# reflip_1_3.net
KiCad netlist of a schematic drawn in EAGLE
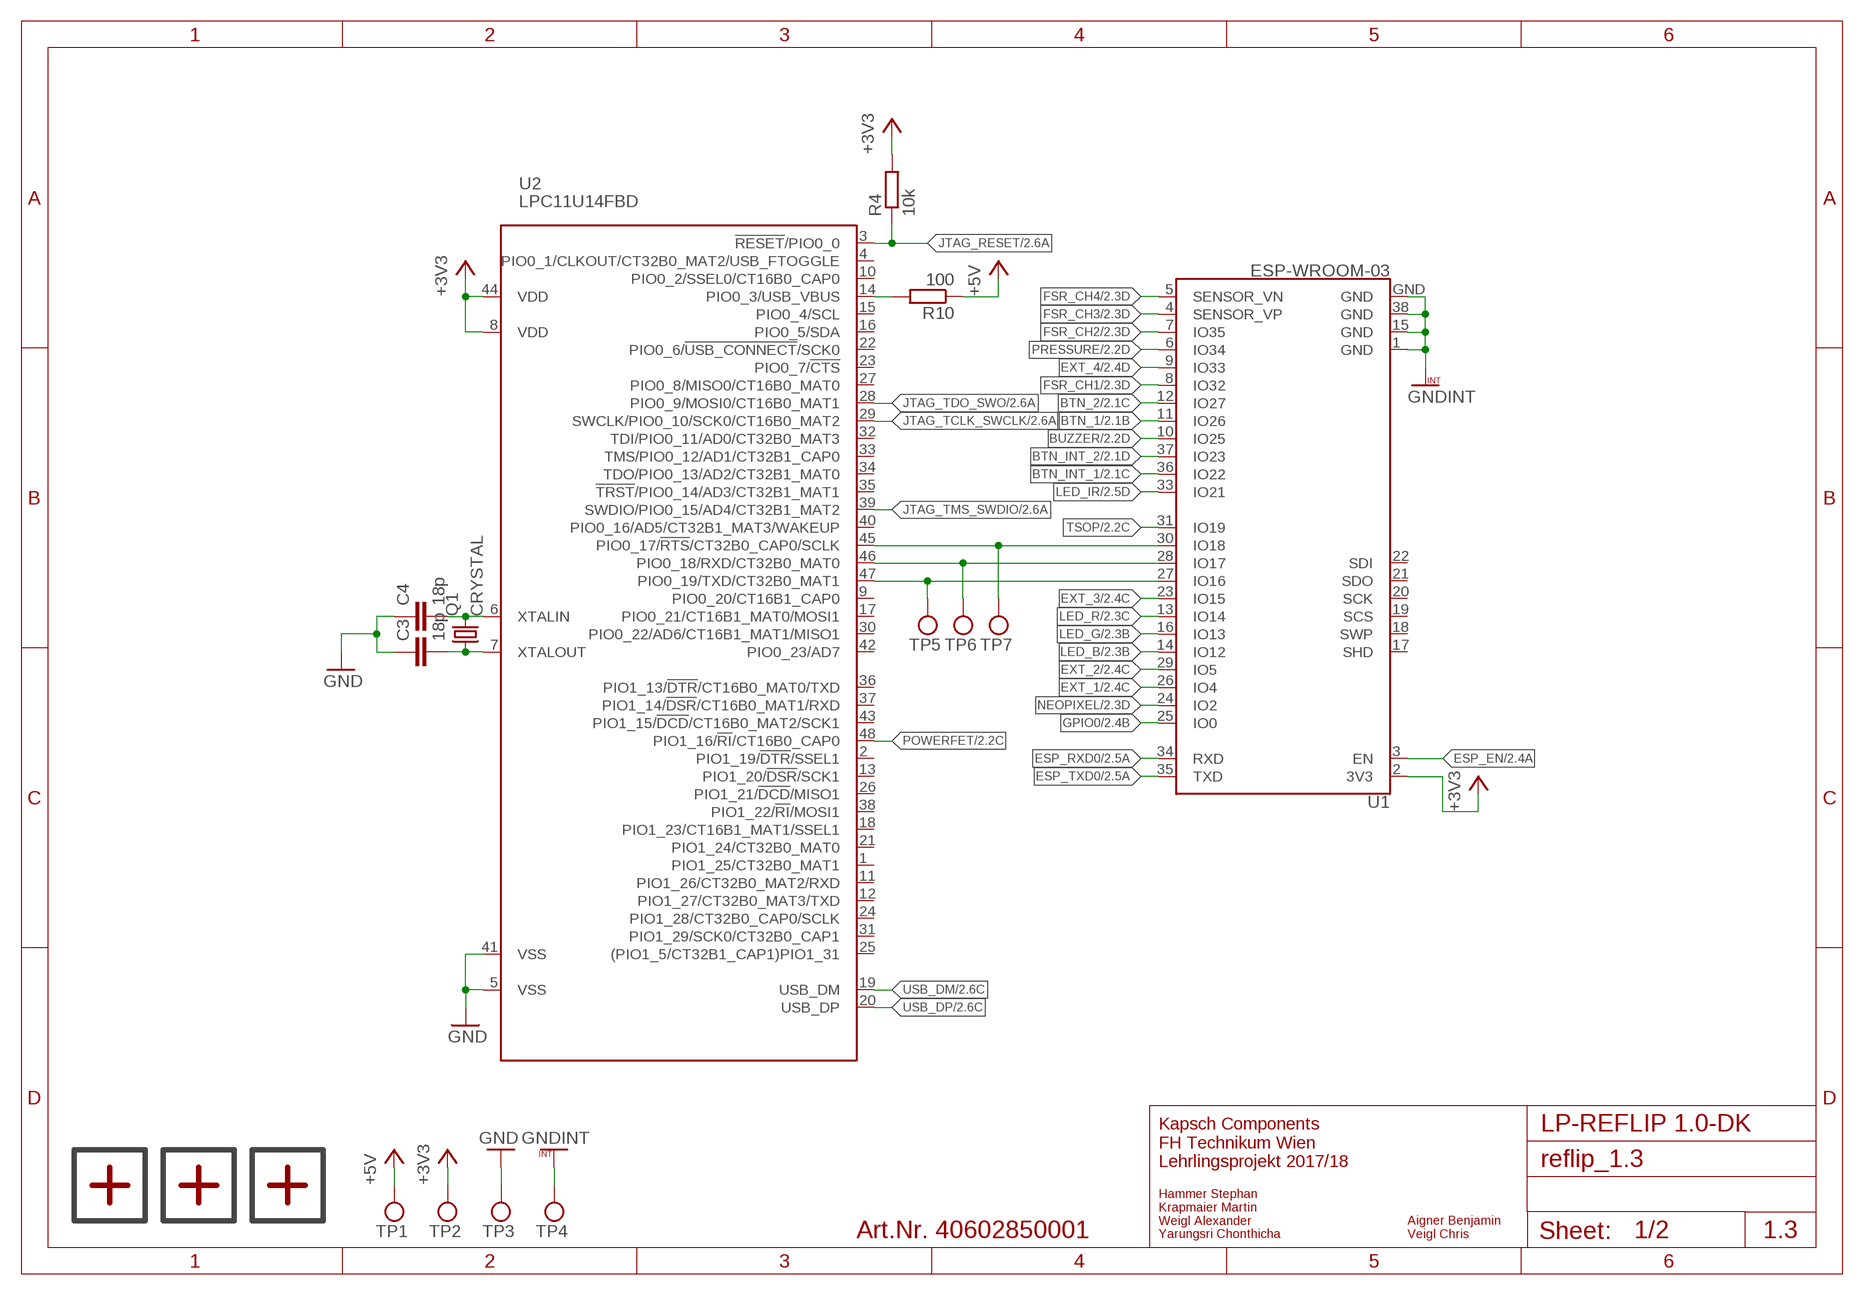
[diagram p0: schematic, sheet 1]
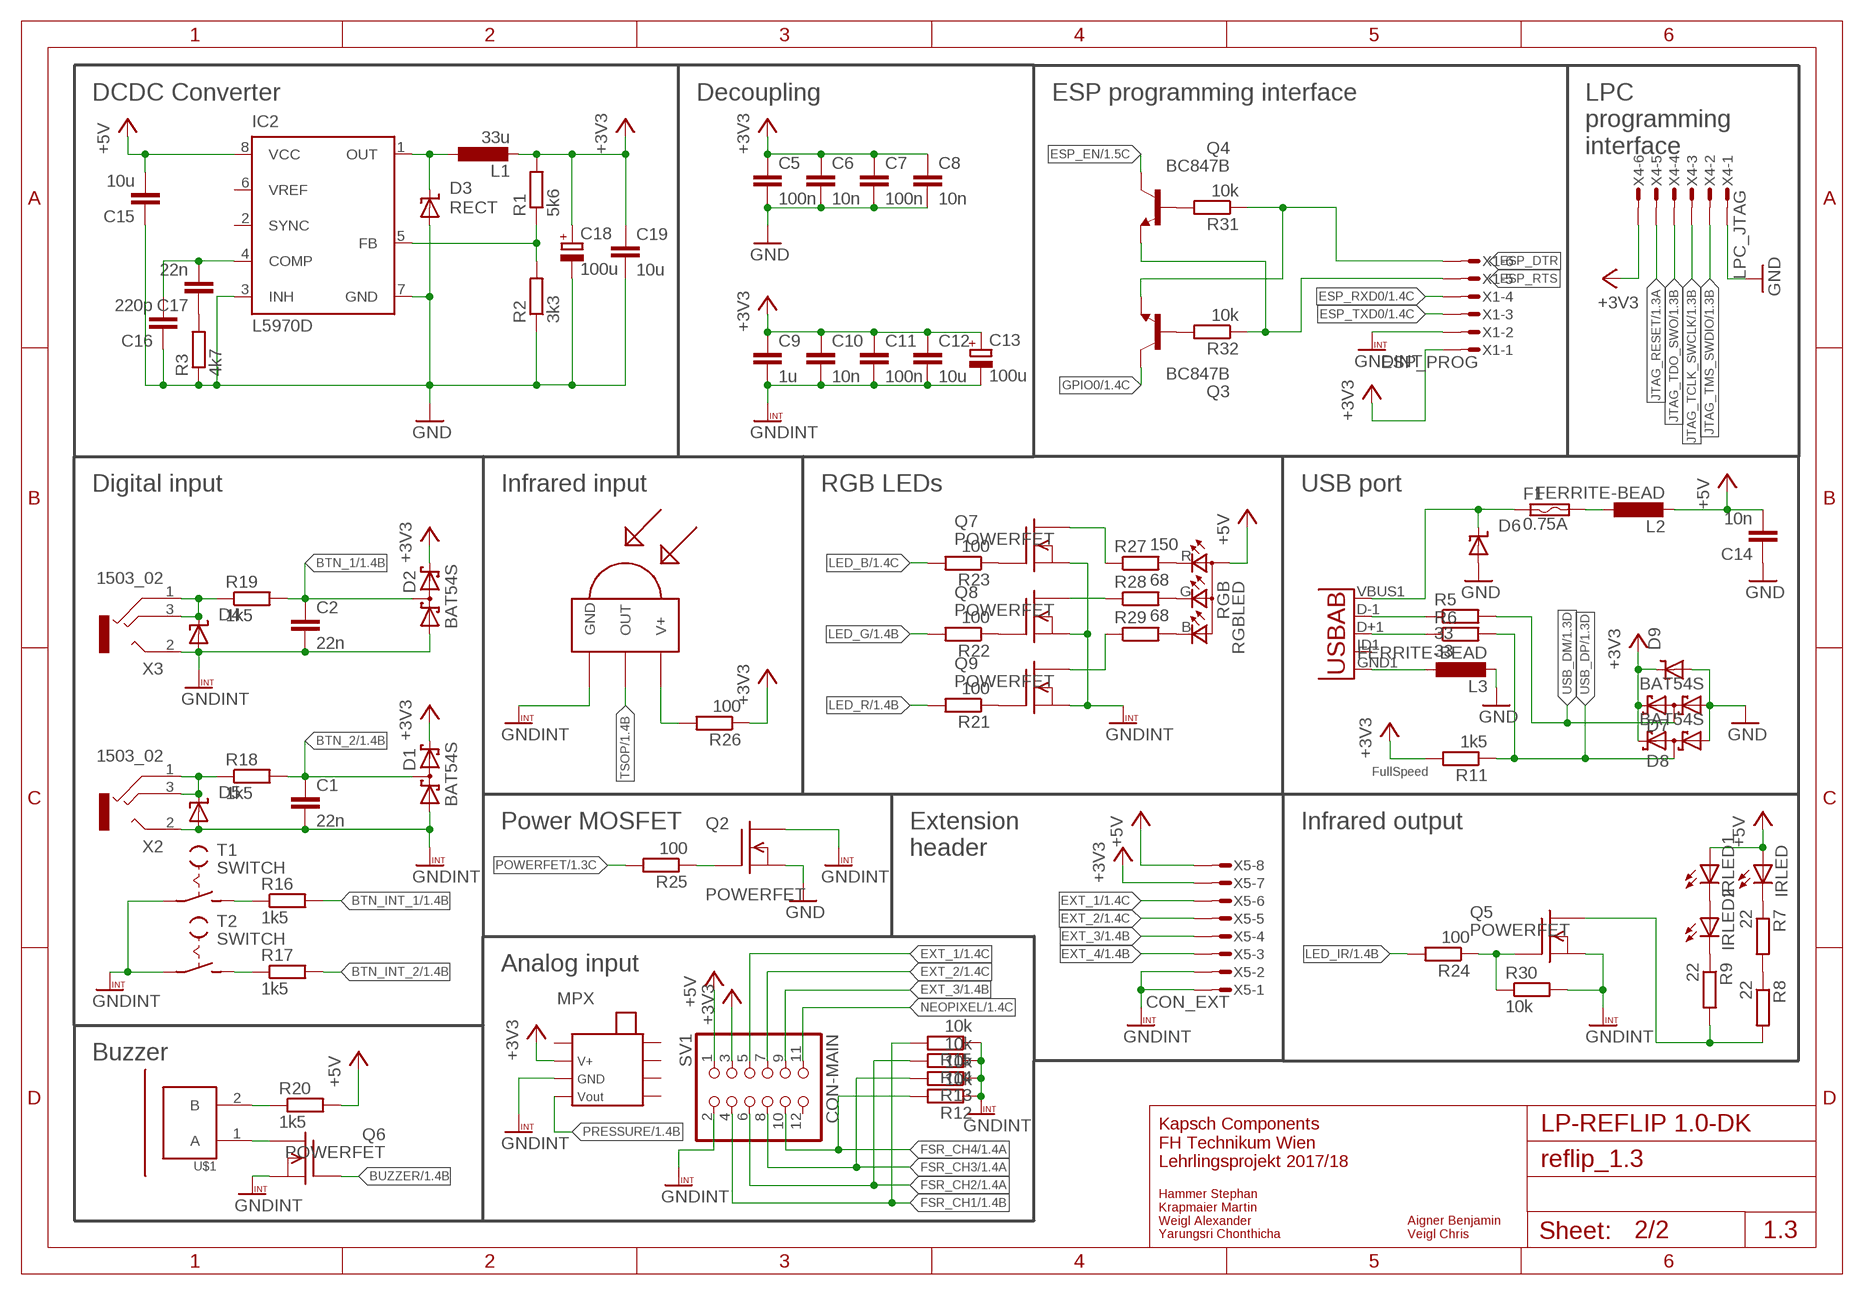
[diagram p1: schematic, sheet 2]

(export (version "E")
  (design (tool "Eeschema 10.0.6"))
  (components
    (comp (ref "C1")
      (value "22n")
      (footprint "eagle-import:C0603")
      (libsource (lib "eagle-import") (part "C-EUC0603"))
    )
    (comp (ref "C2")
      (value "22n")
      (footprint "eagle-import:C0603")
      (libsource (lib "eagle-import") (part "C-EUC0603"))
    )
    (comp (ref "C5")
      (value "100n")
      (footprint "eagle-import:C0603")
      (libsource (lib "eagle-import") (part "C-EUC0603"))
    )
    (comp (ref "C6")
      (value "10n")
      (footprint "eagle-import:C0603")
      (libsource (lib "eagle-import") (part "C-EUC0603"))
    )
    (comp (ref "C7")
      (value "100n")
      (footprint "eagle-import:C0603")
      (libsource (lib "eagle-import") (part "C-EUC0603"))
    )
    (comp (ref "C8")
      (value "10n")
      (footprint "eagle-import:C0603")
      (libsource (lib "eagle-import") (part "C-EUC0603"))
    )
    (comp (ref "C9")
      (value "1u")
      (footprint "eagle-import:C0603")
      (libsource (lib "eagle-import") (part "C-EUC0603"))
    )
    (comp (ref "C10")
      (value "10n")
      (footprint "eagle-import:C0603")
      (libsource (lib "eagle-import") (part "C-EUC0603"))
    )
    (comp (ref "C11")
      (value "100n")
      (footprint "eagle-import:C0603")
      (libsource (lib "eagle-import") (part "C-EUC0603"))
    )
    (comp (ref "C12")
      (value "10u")
      (footprint "eagle-import:C0603")
      (libsource (lib "eagle-import") (part "C-EUC0603"))
    )
    (comp (ref "C13")
      (value "100u")
      (footprint "eagle-import:PANASONIC_D")
      (libsource (lib "eagle-import") (part "CPOL-EUD"))
    )
    (comp (ref "C14")
      (value "10n")
      (footprint "eagle-import:C0603")
      (libsource (lib "eagle-import") (part "C-EUC0603"))
    )
    (comp (ref "C15")
      (value "10u")
      (footprint "eagle-import:C0603")
      (libsource (lib "eagle-import") (part "C-EUC0603"))
    )
    (comp (ref "C16")
      (value "220p")
      (footprint "eagle-import:C0603")
      (libsource (lib "eagle-import") (part "C-EUC0603"))
    )
    (comp (ref "C17")
      (value "22n")
      (footprint "eagle-import:C0603")
      (libsource (lib "eagle-import") (part "C-EUC0603"))
    )
    (comp (ref "C18")
      (value "100u")
      (footprint "eagle-import:PANASONIC_D")
      (libsource (lib "eagle-import") (part "CPOL-EUD"))
    )
    (comp (ref "C19")
      (value "10u")
      (footprint "eagle-import:C0603")
      (libsource (lib "eagle-import") (part "C-EUC0603"))
    )
    (comp (ref "D1")
      (value "BAT54S")
      (footprint "eagle-import:SOT23")
      (libsource (lib "eagle-import") (part "BAT54S"))
    )
    (comp (ref "D2")
      (value "BAT54S")
      (footprint "eagle-import:SOT23")
      (libsource (lib "eagle-import") (part "BAT54S"))
    )
    (comp (ref "D3")
      (value "RECT")
      (footprint "eagle-import:SMBJ")
      (libsource (lib "eagle-import") (part "RECT"))
    )
    (comp (ref "D4")
      (value "TVS-DIODE")
      (footprint "eagle-import:SMBJ")
      (libsource (lib "eagle-import") (part "TVS-DIODE"))
    )
    (comp (ref "D5")
      (value "TVS-DIODE")
      (footprint "eagle-import:SMBJ")
      (libsource (lib "eagle-import") (part "TVS-DIODE"))
    )
    (comp (ref "D6")
      (value "TVS-DIODE")
      (footprint "eagle-import:SMBJ")
      (libsource (lib "eagle-import") (part "TVS-DIODE"))
    )
    (comp (ref "D7")
      (value "BAT54S")
      (footprint "eagle-import:SOT23")
      (libsource (lib "eagle-import") (part "BAT54S"))
    )
    (comp (ref "D8")
      (value "BAT54S")
      (footprint "eagle-import:SOT23")
      (libsource (lib "eagle-import") (part "BAT54S"))
    )
    (comp (ref "D9")
      (value "TVS-DIODE")
      (footprint "eagle-import:SMBJ")
      (libsource (lib "eagle-import") (part "TVS-DIODE"))
    )
    (comp (ref "F1")
      (value "0.75A")
      (footprint "eagle-import:FUSE")
      (libsource (lib "eagle-import") (part "FUSE"))
    )
    (comp (ref "IC2")
      (value "L5970D")
      (footprint "eagle-import:HSOP8")
      (fields (field (name "MF") "STMICROELECTRONICS") (field (name "MPN") "L5973D"))
      (libsource (lib "eagle-import") (part "L5973D"))
    )
    (comp (ref "IRLED")
      (value "IRLED")
      (footprint "eagle-import:IRLED")
      (libsource (lib "eagle-import") (part "IRLED"))
    )
    (comp (ref "IRLED1")
      (value "IRLED")
      (footprint "eagle-import:IRLED")
      (libsource (lib "eagle-import") (part "IRLED"))
    )
    (comp (ref "IRLED2")
      (value "IRLED")
      (footprint "eagle-import:IRLED")
      (libsource (lib "eagle-import") (part "IRLED"))
    )
    (comp (ref "L1")
      (value "33u")
      (footprint "eagle-import:SPULE")
      (libsource (lib "eagle-import") (part "SPULE"))
    )
    (comp (ref "L2")
      (value "FERRITE-BEAD")
      (footprint "eagle-import:FERRITEBEAD")
      (libsource (lib "eagle-import") (part "FERRITE-BEAD"))
    )
    (comp (ref "L3")
      (value "FERRITE-BEAD")
      (footprint "eagle-import:FERRITEBEAD")
      (libsource (lib "eagle-import") (part "FERRITE-BEAD"))
    )
    (comp (ref "MPX")
      (value "MPX_PRESSURE_SENSOR")
      (footprint "eagle-import:MPX_PRESSURE_SENSOR")
      (libsource (lib "eagle-import") (part "MPX_PRESSURE_SENSOR"))
    )
    (comp (ref "Q2")
      (value "POWERFET")
      (footprint "eagle-import:SOT-23")
      (libsource (lib "eagle-import") (part "POWERFET"))
    )
    (comp (ref "Q3")
      (value "BC847B")
      (footprint "eagle-import:SOT23")
      (libsource (lib "eagle-import") (part "BC847B"))
    )
    (comp (ref "Q4")
      (value "BC847B")
      (footprint "eagle-import:SOT23")
      (libsource (lib "eagle-import") (part "BC847B"))
    )
    (comp (ref "Q5")
      (value "POWERFET")
      (footprint "eagle-import:SOT-23")
      (libsource (lib "eagle-import") (part "POWERFET"))
    )
    (comp (ref "Q6")
      (value "POWERFET")
      (footprint "eagle-import:SOT-23")
      (libsource (lib "eagle-import") (part "POWERFET"))
    )
    (comp (ref "Q7")
      (value "POWERFET")
      (footprint "eagle-import:SOT-23")
      (libsource (lib "eagle-import") (part "POWERFET"))
    )
    (comp (ref "Q8")
      (value "POWERFET")
      (footprint "eagle-import:SOT-23")
      (libsource (lib "eagle-import") (part "POWERFET"))
    )
    (comp (ref "Q9")
      (value "POWERFET")
      (footprint "eagle-import:SOT-23")
      (libsource (lib "eagle-import") (part "POWERFET"))
    )
    (comp (ref "R1")
      (value "5k6")
      (footprint "eagle-import:R0603")
      (libsource (lib "eagle-import") (part "R-EU_R0603"))
    )
    (comp (ref "R2")
      (value "3k3")
      (footprint "eagle-import:R0603")
      (libsource (lib "eagle-import") (part "R-EU_R0603"))
    )
    (comp (ref "R3")
      (value "4k7")
      (footprint "eagle-import:R0603")
      (libsource (lib "eagle-import") (part "R-EU_R0603"))
    )
    (comp (ref "R5")
      (value "33")
      (footprint "eagle-import:R0603")
      (libsource (lib "eagle-import") (part "R-EU_R0603"))
    )
    (comp (ref "R6")
      (value "33")
      (footprint "eagle-import:R0603")
      (libsource (lib "eagle-import") (part "R-EU_R0603"))
    )
    (comp (ref "R7")
      (value "22")
      (footprint "eagle-import:R1206")
      (libsource (lib "eagle-import") (part "R-EU_R1206"))
    )
    (comp (ref "R8")
      (value "22")
      (footprint "eagle-import:R1206")
      (libsource (lib "eagle-import") (part "R-EU_R1206"))
    )
    (comp (ref "R9")
      (value "22")
      (footprint "eagle-import:R1206")
      (libsource (lib "eagle-import") (part "R-EU_R1206"))
    )
    (comp (ref "R11")
      (value "1k5")
      (footprint "eagle-import:R0603")
      (libsource (lib "eagle-import") (part "R-EU_R0603"))
    )
    (comp (ref "R12")
      (value "10k")
      (footprint "eagle-import:R0603")
      (libsource (lib "eagle-import") (part "R-EU_R0603"))
    )
    (comp (ref "R13")
      (value "10k")
      (footprint "eagle-import:R0603")
      (libsource (lib "eagle-import") (part "R-EU_R0603"))
    )
    (comp (ref "R14")
      (value "10k")
      (footprint "eagle-import:R0603")
      (libsource (lib "eagle-import") (part "R-EU_R0603"))
    )
    (comp (ref "R15")
      (value "10k")
      (footprint "eagle-import:R0603")
      (libsource (lib "eagle-import") (part "R-EU_R0603"))
    )
    (comp (ref "R16")
      (value "1k5")
      (footprint "eagle-import:R0603")
      (libsource (lib "eagle-import") (part "R-EU_R0603"))
    )
    (comp (ref "R17")
      (value "1k5")
      (footprint "eagle-import:R0603")
      (libsource (lib "eagle-import") (part "R-EU_R0603"))
    )
    (comp (ref "R18")
      (value "1k5")
      (footprint "eagle-import:R0603")
      (libsource (lib "eagle-import") (part "R-EU_R0603"))
    )
    (comp (ref "R19")
      (value "1k5")
      (footprint "eagle-import:R0603")
      (libsource (lib "eagle-import") (part "R-EU_R0603"))
    )
    (comp (ref "R20")
      (value "1k5")
      (footprint "eagle-import:R0603")
      (libsource (lib "eagle-import") (part "R-EU_R0603"))
    )
    (comp (ref "R21")
      (value "100")
      (footprint "eagle-import:R0603")
      (libsource (lib "eagle-import") (part "R-EU_R0603"))
    )
    (comp (ref "R22")
      (value "100")
      (footprint "eagle-import:R0603")
      (libsource (lib "eagle-import") (part "R-EU_R0603"))
    )
    (comp (ref "R23")
      (value "100")
      (footprint "eagle-import:R0603")
      (libsource (lib "eagle-import") (part "R-EU_R0603"))
    )
    (comp (ref "R24")
      (value "100")
      (footprint "eagle-import:R0603")
      (libsource (lib "eagle-import") (part "R-EU_R0603"))
    )
    (comp (ref "R25")
      (value "100")
      (footprint "eagle-import:R0603")
      (libsource (lib "eagle-import") (part "R-EU_R0603"))
    )
    (comp (ref "R26")
      (value "100")
      (footprint "eagle-import:R0603")
      (libsource (lib "eagle-import") (part "R-EU_R0603"))
    )
    (comp (ref "R27")
      (value "150")
      (footprint "eagle-import:R0603")
      (libsource (lib "eagle-import") (part "R-EU_R0603"))
    )
    (comp (ref "R28")
      (value "68")
      (footprint "eagle-import:R0603")
      (libsource (lib "eagle-import") (part "R-EU_R0603"))
    )
    (comp (ref "R29")
      (value "68")
      (footprint "eagle-import:R0603")
      (libsource (lib "eagle-import") (part "R-EU_R0603"))
    )
    (comp (ref "R30")
      (value "10k")
      (footprint "eagle-import:R0603")
      (libsource (lib "eagle-import") (part "R-EU_R0603"))
    )
    (comp (ref "R31")
      (value "10k")
      (footprint "eagle-import:R0603")
      (libsource (lib "eagle-import") (part "R-EU_R0603"))
    )
    (comp (ref "R32")
      (value "10k")
      (footprint "eagle-import:R0603")
      (libsource (lib "eagle-import") (part "R-EU_R0603"))
    )
    (comp (ref "RGB")
      (value "RGBLED")
      (footprint "eagle-import:RGBLED")
      (libsource (lib "eagle-import") (part "RGBLED"))
    )
    (comp (ref "SV1")
      (value "CON-MAIN")
      (footprint "eagle-import:FE06-2W")
      (libsource (lib "eagle-import") (part "CON-MAIN"))
    )
    (comp (ref "T1")
      (value "SWITCH")
      (footprint "eagle-import:SWITCHES")
      (libsource (lib "eagle-import") (part "SWITCH"))
    )
    (comp (ref "T2")
      (value "SWITCH")
      (footprint "eagle-import:SWITCHES")
      (libsource (lib "eagle-import") (part "SWITCH"))
    )
    (comp (ref "U$1")
      (value "PKLCS1212E2400-R1")
      (footprint "eagle-import:BUZZ_PIEZO_SMD")
      (libsource (lib "eagle-import") (part "PKLCS1212E2400-R1"))
    )
    (comp (ref "U$2")
      (value "TSOP4838")
      (footprint "eagle-import:TSOP18XX")
      (libsource (lib "eagle-import") (part "TSOP4838"))
    )
    (comp (ref "U3")
      (value "USB\"\"")
      (footprint "eagle-import:USB-MICRO-SMD")
      (libsource (lib "eagle-import") (part "USB{dblquote}{dblquote}"))
    )
    (comp (ref "X1")
      (value "ESP_PROG")
      (footprint "eagle-import:MICROMATCH-6SMD")
      (libsource (lib "eagle-import") (part "MICROMATCH-6SMD"))
    )
    (comp (ref "X2")
      (value "1503_02")
      (footprint "eagle-import:1503_02")
      (libsource (lib "eagle-import") (part "1503_02"))
    )
    (comp (ref "X3")
      (value "1503_02")
      (footprint "eagle-import:1503_02")
      (libsource (lib "eagle-import") (part "1503_02"))
    )
    (comp (ref "X4")
      (value "LPC_JTAG")
      (footprint "eagle-import:MICROMATCH-6SMD")
      (libsource (lib "eagle-import") (part "MICROMATCH-6SMD"))
    )
    (comp (ref "X5")
      (value "CON_EXT")
      (footprint "eagle-import:MICROMATCH-8-SMD")
      (libsource (lib "eagle-import") (part "MICROMATCH-8SMD"))
    )
    (comp (ref "C3")
      (value "18p")
      (footprint "eagle-import:C0603")
      (libsource (lib "eagle-import") (part "C-EUC0603"))
    )
    (comp (ref "C4")
      (value "18p")
      (footprint "eagle-import:C0603")
      (libsource (lib "eagle-import") (part "C-EUC0603"))
    )
    (comp (ref "Q1")
      (value "CRYSTAL")
      (footprint "eagle-import:CRYSTAL")
      (libsource (lib "eagle-import") (part "CRYSTAL"))
    )
    (comp (ref "R4")
      (value "10k")
      (footprint "eagle-import:R0603")
      (libsource (lib "eagle-import") (part "R-EU_R0603"))
    )
    (comp (ref "R10")
      (value "100")
      (footprint "eagle-import:R0603")
      (libsource (lib "eagle-import") (part "R-EU_R0603"))
    )
    (comp (ref "U$3")
      (value "PASSMARKE")
      (footprint "eagle-import:PASSMARKE")
      (libsource (lib "eagle-import") (part "PASSMARKE"))
    )
    (comp (ref "U$4")
      (value "PASSMARKE")
      (footprint "eagle-import:PASSMARKE")
      (libsource (lib "eagle-import") (part "PASSMARKE"))
    )
    (comp (ref "U$5")
      (value "PASSMARKE")
      (footprint "eagle-import:PASSMARKE")
      (libsource (lib "eagle-import") (part "PASSMARKE"))
    )
    (comp (ref "U$6")
      (value "TP1")
      (footprint "eagle-import:TESTPUNKT")
      (libsource (lib "eagle-import") (part "TESTPUNKT"))
    )
    (comp (ref "U$7")
      (value "TP2")
      (footprint "eagle-import:TESTPUNKT")
      (libsource (lib "eagle-import") (part "TESTPUNKT"))
    )
    (comp (ref "U$8")
      (value "TP3")
      (footprint "eagle-import:TESTPUNKT")
      (libsource (lib "eagle-import") (part "TESTPUNKT"))
    )
    (comp (ref "U$9")
      (value "TP4")
      (footprint "eagle-import:TESTPUNKT")
      (libsource (lib "eagle-import") (part "TESTPUNKT"))
    )
    (comp (ref "U$10")
      (value "TP7")
      (footprint "eagle-import:TESTPUNKT")
      (libsource (lib "eagle-import") (part "TESTPUNKT"))
    )
    (comp (ref "U$11")
      (value "TP6")
      (footprint "eagle-import:TESTPUNKT")
      (libsource (lib "eagle-import") (part "TESTPUNKT"))
    )
    (comp (ref "U$12")
      (value "TP5")
      (footprint "eagle-import:TESTPUNKT")
      (libsource (lib "eagle-import") (part "TESTPUNKT"))
    )
    (comp (ref "U1")
      (value "ESP-WROOM-03")
      (footprint "eagle-import:ESP-WROOM-03")
      (libsource (lib "eagle-import") (part "ESP-WROOM-03"))
    )
    (comp (ref "U2")
      (value "LPC11U14FBD")
      (footprint "eagle-import:SOT313-2")
      (libsource (lib "eagle-import") (part "LPC11U14FBD"))
    )
  )
  (nets
    (net (code "1") (name "+3V3") (class "Default")
      (node (ref "C10") (pin "1") (pinfunction "1_1") (pintype "passive"))
      (node (ref "C11") (pin "1") (pinfunction "1_1") (pintype "passive"))
      (node (ref "C12") (pin "1") (pinfunction "1_1") (pintype "passive"))
      (node (ref "C13") (pin "+") (pinfunction "+_+") (pintype "passive"))
      (node (ref "C18") (pin "+") (pinfunction "+_+") (pintype "passive"))
      (node (ref "C19") (pin "1") (pinfunction "1_1") (pintype "passive"))
      (node (ref "C5") (pin "1") (pinfunction "1_1") (pintype "passive"))
      (node (ref "C6") (pin "1") (pinfunction "1_1") (pintype "passive"))
      (node (ref "C7") (pin "1") (pinfunction "1_1") (pintype "passive"))
      (node (ref "C8") (pin "1") (pinfunction "1_1") (pintype "passive"))
      (node (ref "C9") (pin "1") (pinfunction "1_1") (pintype "passive"))
      (node (ref "D1") (pin "2") (pinfunction "C2_2") (pintype "passive"))
      (node (ref "D2") (pin "2") (pinfunction "C2_2") (pintype "passive"))
      (node (ref "D7") (pin "2") (pinfunction "C2_2") (pintype "passive"))
      (node (ref "D8") (pin "2") (pinfunction "C2_2") (pintype "passive"))
      (node (ref "D9") (pin "C") (pinfunction "C_C") (pintype "passive"))
      (node (ref "L1") (pin "P$2") (pinfunction "2_P$2") (pintype "passive"))
      (node (ref "MPX") (pin "P$2") (pinfunction "V+_P$2") (pintype "power_in"))
      (node (ref "R1") (pin "2") (pinfunction "2_2") (pintype "passive"))
      (node (ref "R11") (pin "2") (pinfunction "2_2") (pintype "passive"))
      (node (ref "R26") (pin "1") (pinfunction "1_1") (pintype "passive"))
      (node (ref "R4") (pin "2") (pinfunction "2_2") (pintype "passive"))
      (node (ref "SV1") (pin "3") (pinfunction "3_3") (pintype "passive"))
      (node (ref "U$7") (pin "P$1") (pinfunction "VCC_P$1") (pintype "bidirectional"))
      (node (ref "U1") (pin "2") (pinfunction "3V3_2") (pintype "bidirectional"))
      (node (ref "U2") (pin "44") (pinfunction "VDD_44") (pintype "power_in"))
      (node (ref "U2") (pin "8") (pinfunction "VDD_8") (pintype "power_in"))
      (node (ref "X1") (pin "1") (pinfunction "S_1") (pintype "passive"))
      (node (ref "X4") (pin "6") (pinfunction "S_6") (pintype "passive"))
      (node (ref "X5") (pin "7") (pinfunction "S_7") (pintype "passive"))
    )
    (net (code "2") (name "+5V") (class "Default")
      (node (ref "C14") (pin "2") (pinfunction "2_2") (pintype "passive"))
      (node (ref "C15") (pin "2") (pinfunction "2_2") (pintype "passive"))
      (node (ref "IC2") (pin "8") (pinfunction "VCC_8") (pintype "input"))
      (node (ref "IRLED") (pin "A") (pinfunction "A_A") (pintype "passive"))
      (node (ref "IRLED1") (pin "A") (pinfunction "A_A") (pintype "passive"))
      (node (ref "L2") (pin "P$2") (pinfunction "2_P$2") (pintype "passive"))
      (node (ref "R10") (pin "1") (pinfunction "1_1") (pintype "passive"))
      (node (ref "R20") (pin "2") (pinfunction "2_2") (pintype "passive"))
      (node (ref "RGB") (pin "CA") (pinfunction "A2_CA") (pintype "passive"))
      (node (ref "SV1") (pin "1") (pinfunction "1_1") (pintype "passive"))
      (node (ref "U$6") (pin "P$1") (pinfunction "VCC_P$1") (pintype "bidirectional"))
      (node (ref "X5") (pin "8") (pinfunction "S_8") (pintype "passive"))
    )
    (net (code "3") (name "BTN_1") (class "Default")
      (node (ref "C2") (pin "1") (pinfunction "1_1") (pintype "passive"))
      (node (ref "D2") (pin "3") (pinfunction "C1A2_3") (pintype "passive"))
      (node (ref "R19") (pin "2") (pinfunction "2_2") (pintype "passive"))
      (node (ref "U1") (pin "11") (pinfunction "IO26_11") (pintype "bidirectional"))
    )
    (net (code "4") (name "BTN_2") (class "Default")
      (node (ref "C1") (pin "1") (pinfunction "1_1") (pintype "passive"))
      (node (ref "D1") (pin "3") (pinfunction "C1A2_3") (pintype "passive"))
      (node (ref "R18") (pin "2") (pinfunction "2_2") (pintype "passive"))
      (node (ref "U1") (pin "12") (pinfunction "IO27_12") (pintype "bidirectional"))
    )
    (net (code "5") (name "BTN_INT_1") (class "Default")
      (node (ref "R16") (pin "2") (pinfunction "2_2") (pintype "passive"))
      (node (ref "U1") (pin "36") (pinfunction "IO22_36") (pintype "bidirectional"))
    )
    (net (code "6") (name "BTN_INT_2") (class "Default")
      (node (ref "R17") (pin "2") (pinfunction "2_2") (pintype "passive"))
      (node (ref "U1") (pin "37") (pinfunction "IO23_37") (pintype "bidirectional"))
    )
    (net (code "7") (name "BUZZER") (class "Default")
      (node (ref "Q6") (pin "1") (pinfunction "G_1") (pintype "passive"))
      (node (ref "U1") (pin "10") (pinfunction "IO25_10") (pintype "bidirectional"))
    )
    (net (code "8") (name "ESP_DTR") (class "Default")
      (node (ref "Q3") (pin "2") (pinfunction "E_2") (pintype "passive"))
      (node (ref "R31") (pin "1") (pinfunction "1_1") (pintype "passive"))
      (node (ref "X1") (pin "6") (pinfunction "S_6") (pintype "passive"))
    )
    (net (code "9") (name "ESP_EN") (class "Default")
      (node (ref "Q4") (pin "3") (pinfunction "C_3") (pintype "passive"))
      (node (ref "U1") (pin "3") (pinfunction "EN_3") (pintype "bidirectional"))
    )
    (net (code "10") (name "ESP_RTS") (class "Default")
      (node (ref "Q4") (pin "2") (pinfunction "E_2") (pintype "passive"))
      (node (ref "R32") (pin "1") (pinfunction "1_1") (pintype "passive"))
      (node (ref "X1") (pin "5") (pinfunction "S_5") (pintype "passive"))
    )
    (net (code "11") (name "ESP_RXD0") (class "Default")
      (node (ref "U1") (pin "34") (pinfunction "RXD_34") (pintype "bidirectional"))
      (node (ref "X1") (pin "4") (pinfunction "S_4") (pintype "passive"))
    )
    (net (code "12") (name "ESP_TXD0") (class "Default")
      (node (ref "U1") (pin "35") (pinfunction "TXD_35") (pintype "bidirectional"))
      (node (ref "X1") (pin "3") (pinfunction "S_3") (pintype "passive"))
    )
    (net (code "13") (name "EXT_1") (class "Default")
      (node (ref "SV1") (pin "5") (pinfunction "5_5") (pintype "passive"))
      (node (ref "U1") (pin "26") (pinfunction "IO4_26") (pintype "bidirectional"))
      (node (ref "X5") (pin "6") (pinfunction "S_6") (pintype "passive"))
    )
    (net (code "14") (name "EXT_2") (class "Default")
      (node (ref "SV1") (pin "7") (pinfunction "7_7") (pintype "passive"))
      (node (ref "U1") (pin "29") (pinfunction "IO5_29") (pintype "bidirectional"))
      (node (ref "X5") (pin "5") (pinfunction "S_5") (pintype "passive"))
    )
    (net (code "15") (name "EXT_3") (class "Default")
      (node (ref "SV1") (pin "9") (pinfunction "9_9") (pintype "passive"))
      (node (ref "U1") (pin "23") (pinfunction "IO15_23") (pintype "bidirectional"))
      (node (ref "X5") (pin "4") (pinfunction "S_4") (pintype "passive"))
    )
    (net (code "16") (name "EXT_4") (class "Default")
      (node (ref "U1") (pin "9") (pinfunction "IO33_9") (pintype "bidirectional"))
      (node (ref "X5") (pin "3") (pinfunction "S_3") (pintype "passive"))
    )
    (net (code "17") (name "FSR_CH1") (class "Default")
      (node (ref "R15") (pin "2") (pinfunction "2_2") (pintype "passive"))
      (node (ref "SV1") (pin "4") (pinfunction "4_4") (pintype "passive"))
      (node (ref "U1") (pin "8") (pinfunction "IO32_8") (pintype "bidirectional"))
    )
    (net (code "18") (name "FSR_CH2") (class "Default")
      (node (ref "R14") (pin "2") (pinfunction "2_2") (pintype "passive"))
      (node (ref "SV1") (pin "6") (pinfunction "6_6") (pintype "passive"))
      (node (ref "U1") (pin "7") (pinfunction "IO35_7") (pintype "bidirectional"))
    )
    (net (code "19") (name "FSR_CH3") (class "Default")
      (node (ref "R13") (pin "2") (pinfunction "2_2") (pintype "passive"))
      (node (ref "SV1") (pin "8") (pinfunction "8_8") (pintype "passive"))
      (node (ref "U1") (pin "4") (pinfunction "SENSOR_VP_4") (pintype "bidirectional"))
    )
    (net (code "20") (name "FSR_CH4") (class "Default")
      (node (ref "R12") (pin "2") (pinfunction "2_2") (pintype "passive"))
      (node (ref "SV1") (pin "10") (pinfunction "10_10") (pintype "passive"))
      (node (ref "U1") (pin "5") (pinfunction "SENSOR_VN_5") (pintype "bidirectional"))
    )
    (net (code "21") (name "GND") (class "Default")
      (node (ref "C14") (pin "1") (pinfunction "1_1") (pintype "passive"))
      (node (ref "C15") (pin "1") (pinfunction "1_1") (pintype "passive"))
      (node (ref "C16") (pin "1") (pinfunction "1_1") (pintype "passive"))
      (node (ref "C18") (pin "-") (pinfunction "-_-") (pintype "passive"))
      (node (ref "C19") (pin "2") (pinfunction "2_2") (pintype "passive"))
      (node (ref "C3") (pin "1") (pinfunction "1_1") (pintype "passive"))
      (node (ref "C4") (pin "1") (pinfunction "1_1") (pintype "passive"))
      (node (ref "C5") (pin "2") (pinfunction "2_2") (pintype "passive"))
      (node (ref "C6") (pin "2") (pinfunction "2_2") (pintype "passive"))
      (node (ref "C7") (pin "2") (pinfunction "2_2") (pintype "passive"))
      (node (ref "C8") (pin "2") (pinfunction "2_2") (pintype "passive"))
      (node (ref "D3") (pin "A") (pinfunction "A_A") (pintype "passive"))
      (node (ref "D6") (pin "A") (pinfunction "A_A") (pintype "passive"))
      (node (ref "D7") (pin "1") (pinfunction "A1_1") (pintype "passive"))
      (node (ref "D8") (pin "1") (pinfunction "A1_1") (pintype "passive"))
      (node (ref "D9") (pin "A") (pinfunction "A_A") (pintype "passive"))
      (node (ref "IC2") (pin "3") (pinfunction "INH_3") (pintype "input"))
      (node (ref "IC2") (pin "7") (pinfunction "GND_7") (pintype "power_in"))
      (node (ref "L3") (pin "P$2") (pinfunction "2_P$2") (pintype "passive"))
      (node (ref "Q2") (pin "2") (pinfunction "S_2") (pintype "passive"))
      (node (ref "R2") (pin "1") (pinfunction "1_1") (pintype "passive"))
      (node (ref "R3") (pin "1") (pinfunction "1_1") (pintype "passive"))
      (node (ref "U$8") (pin "P$1") (pinfunction "VCC_P$1") (pintype "bidirectional"))
      (node (ref "U2") (pin "41") (pinfunction "VSS_41") (pintype "power_in"))
      (node (ref "U2") (pin "5") (pinfunction "VSS_5") (pintype "power_in"))
      (node (ref "X4") (pin "1") (pinfunction "S_1") (pintype "passive"))
    )
    (net (code "22") (name "GNDINT") (class "Default")
      (node (ref "C1") (pin "2") (pinfunction "2_2") (pintype "passive"))
      (node (ref "C10") (pin "2") (pinfunction "2_2") (pintype "passive"))
      (node (ref "C11") (pin "2") (pinfunction "2_2") (pintype "passive"))
      (node (ref "C12") (pin "2") (pinfunction "2_2") (pintype "passive"))
      (node (ref "C13") (pin "-") (pinfunction "-_-") (pintype "passive"))
      (node (ref "C2") (pin "2") (pinfunction "2_2") (pintype "passive"))
      (node (ref "C9") (pin "2") (pinfunction "2_2") (pintype "passive"))
      (node (ref "D1") (pin "1") (pinfunction "A1_1") (pintype "passive"))
      (node (ref "D2") (pin "1") (pinfunction "A1_1") (pintype "passive"))
      (node (ref "D4") (pin "A") (pinfunction "A_A") (pintype "passive"))
      (node (ref "D5") (pin "A") (pinfunction "A_A") (pintype "passive"))
      (node (ref "MPX") (pin "P$3") (pinfunction "GND_P$3") (pintype "power_in"))
      (node (ref "Q2") (pin "3") (pinfunction "D_3") (pintype "passive"))
      (node (ref "Q5") (pin "2") (pinfunction "S_2") (pintype "passive"))
      (node (ref "Q6") (pin "2") (pinfunction "S_2") (pintype "passive"))
      (node (ref "Q7") (pin "2") (pinfunction "S_2") (pintype "passive"))
      (node (ref "Q8") (pin "2") (pinfunction "S_2") (pintype "passive"))
      (node (ref "Q9") (pin "2") (pinfunction "S_2") (pintype "passive"))
      (node (ref "R12") (pin "1") (pinfunction "1_1") (pintype "passive"))
      (node (ref "R13") (pin "1") (pinfunction "1_1") (pintype "passive"))
      (node (ref "R14") (pin "1") (pinfunction "1_1") (pintype "passive"))
      (node (ref "R15") (pin "1") (pinfunction "1_1") (pintype "passive"))
      (node (ref "R30") (pin "2") (pinfunction "2_2") (pintype "passive"))
      (node (ref "SV1") (pin "2") (pinfunction "2_2") (pintype "passive"))
      (node (ref "T1") (pin "P$3") (pinfunction "P_P$3") (pintype "passive"))
      (node (ref "T2") (pin "P$3") (pinfunction "P_P$3") (pintype "passive"))
      (node (ref "U$2") (pin "GND") (pinfunction "GND_GND") (pintype "bidirectional"))
      (node (ref "U$9") (pin "P$1") (pinfunction "VCC_P$1") (pintype "bidirectional"))
      (node (ref "U1") (pin "1") (pinfunction "GND_1") (pintype "bidirectional"))
      (node (ref "U1") (pin "15") (pinfunction "GND_15") (pintype "bidirectional"))
      (node (ref "U1") (pin "38") (pinfunction "GND_38") (pintype "bidirectional"))
      (node (ref "U1") (pin "GND") (pinfunction "GND_GND") (pintype "bidirectional"))
      (node (ref "X1") (pin "2") (pinfunction "S_2") (pintype "passive"))
      (node (ref "X2") (pin "2") (pinfunction "2_2") (pintype "passive"))
      (node (ref "X3") (pin "2") (pinfunction "2_2") (pintype "passive"))
      (node (ref "X5") (pin "1") (pinfunction "S_1") (pintype "passive"))
      (node (ref "X5") (pin "2") (pinfunction "S_2") (pintype "passive"))
    )
    (net (code "23") (name "GPIO0") (class "Default")
      (node (ref "Q3") (pin "3") (pinfunction "C_3") (pintype "passive"))
      (node (ref "U1") (pin "25") (pinfunction "IO0_25") (pintype "bidirectional"))
    )
    (net (code "24") (name "JTAG_RESET") (class "Default")
      (node (ref "R4") (pin "1") (pinfunction "1_1") (pintype "passive"))
      (node (ref "U2") (pin "3") (pinfunction "~{RESET}/PIO0_0_3") (pintype "bidirectional"))
      (node (ref "X4") (pin "5") (pinfunction "S_5") (pintype "passive"))
    )
    (net (code "25") (name "JTAG_TCLK_SWCLK") (class "Default")
      (node (ref "U2") (pin "29") (pinfunction "SWCLK/PIO0_10/SCK0/CT16B0_MAT2_29") (pintype "bidirectional"))
      (node (ref "X4") (pin "3") (pinfunction "S_3") (pintype "passive"))
    )
    (net (code "26") (name "JTAG_TDO_SWO") (class "Default")
      (node (ref "U2") (pin "28") (pinfunction "PIO0_9/MOSI0/CT16B0_MAT1_28") (pintype "bidirectional"))
      (node (ref "X4") (pin "4") (pinfunction "S_4") (pintype "passive"))
    )
    (net (code "27") (name "JTAG_TMS_SWDIO") (class "Default")
      (node (ref "U2") (pin "39") (pinfunction "SWDIO/PIO0_15/AD4/CT32B1_MAT2_39") (pintype "bidirectional"))
      (node (ref "X4") (pin "2") (pinfunction "S_2") (pintype "passive"))
    )
    (net (code "28") (name "LED_B") (class "Default")
      (node (ref "R23") (pin "2") (pinfunction "2_2") (pintype "passive"))
      (node (ref "U1") (pin "14") (pinfunction "IO12_14") (pintype "bidirectional"))
    )
    (net (code "29") (name "LED_G") (class "Default")
      (node (ref "R22") (pin "2") (pinfunction "2_2") (pintype "passive"))
      (node (ref "U1") (pin "16") (pinfunction "IO13_16") (pintype "bidirectional"))
    )
    (net (code "30") (name "LED_IR") (class "Default")
      (node (ref "R24") (pin "2") (pinfunction "2_2") (pintype "passive"))
      (node (ref "U1") (pin "33") (pinfunction "IO21_33") (pintype "bidirectional"))
    )
    (net (code "31") (name "LED_R") (class "Default")
      (node (ref "R21") (pin "2") (pinfunction "2_2") (pintype "passive"))
      (node (ref "U1") (pin "13") (pinfunction "IO14_13") (pintype "bidirectional"))
    )
    (net (code "32") (name "NEOPIXEL") (class "Default")
      (node (ref "SV1") (pin "11") (pinfunction "11_11") (pintype "passive"))
      (node (ref "U1") (pin "24") (pinfunction "IO2_24") (pintype "bidirectional"))
    )
    (net (code "33") (name "Net-(C17-Pad1)") (class "Default")
      (node (ref "C17") (pin "1") (pinfunction "1_1") (pintype "passive"))
      (node (ref "R3") (pin "2") (pinfunction "2_2") (pintype "passive"))
    )
    (net (code "34") (name "Net-(D4-PadC)") (class "Default")
      (node (ref "D4") (pin "C") (pinfunction "C_C") (pintype "passive"))
      (node (ref "R19") (pin "1") (pinfunction "1_1") (pintype "passive"))
      (node (ref "X3") (pin "1") (pinfunction "1_1") (pintype "passive"))
      (node (ref "X3") (pin "3") (pinfunction "3_3") (pintype "passive"))
    )
    (net (code "35") (name "Net-(D5-PadC)") (class "Default")
      (node (ref "D5") (pin "C") (pinfunction "C_C") (pintype "passive"))
      (node (ref "R18") (pin "1") (pinfunction "1_1") (pintype "passive"))
      (node (ref "X2") (pin "1") (pinfunction "1_1") (pintype "passive"))
      (node (ref "X2") (pin "3") (pinfunction "3_3") (pintype "passive"))
    )
    (net (code "36") (name "Net-(F1-1)") (class "Default")
      (node (ref "D6") (pin "C") (pinfunction "C_C") (pintype "passive"))
      (node (ref "F1") (pin "P$1") (pinfunction "1_P$1") (pintype "passive"))
      (node (ref "U3") (pin "VBUS1") (pinfunction "VBUS_VBUS1") (pintype "bidirectional"))
    )
    (net (code "37") (name "Net-(F1-2)") (class "Default")
      (node (ref "F1") (pin "P$2") (pinfunction "2_P$2") (pintype "passive"))
      (node (ref "L2") (pin "P$1") (pinfunction "1_P$1") (pintype "passive"))
    )
    (net (code "38") (name "Net-(IC2B-COMP)") (class "Default")
      (node (ref "C16") (pin "2") (pinfunction "2_2") (pintype "passive"))
      (node (ref "C17") (pin "2") (pinfunction "2_2") (pintype "passive"))
      (node (ref "IC2") (pin "4") (pinfunction "COMP_4") (pintype "passive"))
    )
    (net (code "39") (name "Net-(IC2B-FB)") (class "Default")
      (node (ref "IC2") (pin "5") (pinfunction "FB_5") (pintype "input"))
      (node (ref "R1") (pin "1") (pinfunction "1_1") (pintype "passive"))
      (node (ref "R2") (pin "2") (pinfunction "2_2") (pintype "passive"))
    )
    (net (code "40") (name "Net-(IC2B-OUT)") (class "Default")
      (node (ref "D3") (pin "C") (pinfunction "C_C") (pintype "passive"))
      (node (ref "IC2") (pin "1") (pinfunction "OUT_1") (pintype "output"))
      (node (ref "L1") (pin "P$1") (pinfunction "1_P$1") (pintype "passive"))
    )
    (net (code "41") (name "Net-(IRLED-PadC)") (class "Default")
      (node (ref "IRLED") (pin "C") (pinfunction "C_C") (pintype "passive"))
      (node (ref "R7") (pin "1") (pinfunction "1_1") (pintype "passive"))
    )
    (net (code "42") (name "Net-(IRLED1-PadC)") (class "Default")
      (node (ref "IRLED1") (pin "C") (pinfunction "C_C") (pintype "passive"))
      (node (ref "IRLED2") (pin "A") (pinfunction "A_A") (pintype "passive"))
    )
    (net (code "43") (name "Net-(IRLED2-PadC)") (class "Default")
      (node (ref "IRLED2") (pin "C") (pinfunction "C_C") (pintype "passive"))
      (node (ref "R9") (pin "1") (pinfunction "1_1") (pintype "passive"))
    )
    (net (code "44") (name "Net-(L3-1)") (class "Default")
      (node (ref "L3") (pin "P$1") (pinfunction "1_P$1") (pintype "passive"))
      (node (ref "U3") (pin "GND1") (pinfunction "GND_GND1") (pintype "bidirectional"))
    )
    (net (code "45") (name "Net-(Q1-1)") (class "Default")
      (node (ref "C3") (pin "2") (pinfunction "2_2") (pintype "passive"))
      (node (ref "Q1") (pin "P$1") (pinfunction "1_P$1") (pintype "passive"))
      (node (ref "U2") (pin "7") (pinfunction "XTALOUT_7") (pintype "passive"))
    )
    (net (code "46") (name "Net-(Q1-2)") (class "Default")
      (node (ref "C4") (pin "2") (pinfunction "2_2") (pintype "passive"))
      (node (ref "Q1") (pin "P$2") (pinfunction "2_P$2") (pintype "passive"))
      (node (ref "U2") (pin "6") (pinfunction "XTALIN_6") (pintype "passive"))
    )
    (net (code "47") (name "Net-(Q2-G)") (class "Default")
      (node (ref "Q2") (pin "1") (pinfunction "G_1") (pintype "passive"))
      (node (ref "R25") (pin "1") (pinfunction "1_1") (pintype "passive"))
    )
    (net (code "48") (name "Net-(Q3-B)") (class "Default")
      (node (ref "Q3") (pin "1") (pinfunction "B_1") (pintype "passive"))
      (node (ref "R32") (pin "2") (pinfunction "2_2") (pintype "passive"))
    )
    (net (code "49") (name "Net-(Q4-B)") (class "Default")
      (node (ref "Q4") (pin "1") (pinfunction "B_1") (pintype "passive"))
      (node (ref "R31") (pin "2") (pinfunction "2_2") (pintype "passive"))
    )
    (net (code "50") (name "Net-(Q5-D)") (class "Default")
      (node (ref "Q5") (pin "3") (pinfunction "D_3") (pintype "passive"))
      (node (ref "R8") (pin "2") (pinfunction "2_2") (pintype "passive"))
      (node (ref "R9") (pin "2") (pinfunction "2_2") (pintype "passive"))
    )
    (net (code "51") (name "Net-(Q5-G)") (class "Default")
      (node (ref "Q5") (pin "1") (pinfunction "G_1") (pintype "passive"))
      (node (ref "R24") (pin "1") (pinfunction "1_1") (pintype "passive"))
      (node (ref "R30") (pin "1") (pinfunction "1_1") (pintype "passive"))
    )
    (net (code "52") (name "Net-(Q6-D)") (class "Default")
      (node (ref "Q6") (pin "3") (pinfunction "D_3") (pintype "passive"))
      (node (ref "U$1") (pin "1") (pinfunction "A_1") (pintype "bidirectional"))
    )
    (net (code "53") (name "Net-(Q7-D)") (class "Default")
      (node (ref "Q7") (pin "3") (pinfunction "D_3") (pintype "passive"))
      (node (ref "R27") (pin "1") (pinfunction "1_1") (pintype "passive"))
    )
    (net (code "54") (name "Net-(Q7-G)") (class "Default")
      (node (ref "Q7") (pin "1") (pinfunction "G_1") (pintype "passive"))
      (node (ref "R23") (pin "1") (pinfunction "1_1") (pintype "passive"))
    )
    (net (code "55") (name "Net-(Q8-D)") (class "Default")
      (node (ref "Q8") (pin "3") (pinfunction "D_3") (pintype "passive"))
      (node (ref "R28") (pin "1") (pinfunction "1_1") (pintype "passive"))
    )
    (net (code "56") (name "Net-(Q8-G)") (class "Default")
      (node (ref "Q8") (pin "1") (pinfunction "G_1") (pintype "passive"))
      (node (ref "R22") (pin "1") (pinfunction "1_1") (pintype "passive"))
    )
    (net (code "57") (name "Net-(Q9-D)") (class "Default")
      (node (ref "Q9") (pin "3") (pinfunction "D_3") (pintype "passive"))
      (node (ref "R29") (pin "1") (pinfunction "1_1") (pintype "passive"))
    )
    (net (code "58") (name "Net-(Q9-G)") (class "Default")
      (node (ref "Q9") (pin "1") (pinfunction "G_1") (pintype "passive"))
      (node (ref "R21") (pin "1") (pinfunction "1_1") (pintype "passive"))
    )
    (net (code "59") (name "Net-(R7-Pad2)") (class "Default")
      (node (ref "R7") (pin "2") (pinfunction "2_2") (pintype "passive"))
      (node (ref "R8") (pin "1") (pinfunction "1_1") (pintype "passive"))
    )
    (net (code "60") (name "Net-(RGB-CBLUE)") (class "Default")
      (node (ref "R29") (pin "2") (pinfunction "2_2") (pintype "passive"))
      (node (ref "RGB") (pin "B") (pinfunction "CBLUE_B") (pintype "passive"))
    )
    (net (code "61") (name "Net-(RGB-CGREEN)") (class "Default")
      (node (ref "R28") (pin "2") (pinfunction "2_2") (pintype "passive"))
      (node (ref "RGB") (pin "G") (pinfunction "CGREEN_G") (pintype "passive"))
    )
    (net (code "62") (name "Net-(RGB-CRED)") (class "Default")
      (node (ref "R27") (pin "2") (pinfunction "2_2") (pintype "passive"))
      (node (ref "RGB") (pin "R") (pinfunction "CRED_R") (pintype "passive"))
    )
    (net (code "63") (name "Net-(T1-S)") (class "Default")
      (node (ref "R16") (pin "1") (pinfunction "1_1") (pintype "passive"))
      (node (ref "T1") (pin "P$4") (pinfunction "S_P$4") (pintype "passive"))
    )
    (net (code "64") (name "Net-(T2-S)") (class "Default")
      (node (ref "R17") (pin "1") (pinfunction "1_1") (pintype "passive"))
      (node (ref "T2") (pin "P$4") (pinfunction "S_P$4") (pintype "passive"))
    )
    (net (code "65") (name "Net-(U$1-B)") (class "Default")
      (node (ref "R20") (pin "1") (pinfunction "1_1") (pintype "passive"))
      (node (ref "U$1") (pin "2") (pinfunction "B_2") (pintype "bidirectional"))
    )
    (net (code "66") (name "Net-(U$2-V+)") (class "Default")
      (node (ref "R26") (pin "2") (pinfunction "2_2") (pintype "passive"))
      (node (ref "U$2") (pin "VCC") (pinfunction "V+_VCC") (pintype "bidirectional"))
    )
    (net (code "67") (name "Net-(U$10-VCC)") (class "Default")
      (node (ref "U$10") (pin "P$1") (pinfunction "VCC_P$1") (pintype "bidirectional"))
      (node (ref "U1") (pin "30") (pinfunction "IO18_30") (pintype "bidirectional"))
      (node (ref "U2") (pin "45") (pinfunction "PIO0_17/~{RTS}/CT32B0_CAP0/SCLK_45") (pintype "bidirectional"))
    )
    (net (code "68") (name "Net-(U$11-VCC)") (class "Default")
      (node (ref "U$11") (pin "P$1") (pinfunction "VCC_P$1") (pintype "bidirectional"))
      (node (ref "U1") (pin "28") (pinfunction "IO17_28") (pintype "bidirectional"))
      (node (ref "U2") (pin "46") (pinfunction "PIO0_18/RXD/CT32B0_MAT0_46") (pintype "bidirectional"))
    )
    (net (code "69") (name "Net-(U$12-VCC)") (class "Default")
      (node (ref "U$12") (pin "P$1") (pinfunction "VCC_P$1") (pintype "bidirectional"))
      (node (ref "U1") (pin "27") (pinfunction "IO16_27") (pintype "bidirectional"))
      (node (ref "U2") (pin "47") (pinfunction "PIO0_19/TXD/CT32B0_MAT1_47") (pintype "bidirectional"))
    )
    (net (code "70") (name "Net-(U2-PIO0_3{slash}USB_VBUS)") (class "Default")
      (node (ref "R10") (pin "2") (pinfunction "2_2") (pintype "passive"))
      (node (ref "U2") (pin "14") (pinfunction "PIO0_3/USB_VBUS_14") (pintype "bidirectional"))
    )
    (net (code "71") (name "Net-(U3-D+)") (class "Default")
      (node (ref "R6") (pin "1") (pinfunction "1_1") (pintype "passive"))
      (node (ref "U3") (pin "D+1") (pinfunction "D+_D+1") (pintype "bidirectional"))
    )
    (net (code "72") (name "Net-(U3-D-)") (class "Default")
      (node (ref "R5") (pin "1") (pinfunction "1_1") (pintype "passive"))
      (node (ref "U3") (pin "D-1") (pinfunction "D-_D-1") (pintype "bidirectional"))
    )
    (net (code "73") (name "POWERFET") (class "Default")
      (node (ref "R25") (pin "2") (pinfunction "2_2") (pintype "passive"))
      (node (ref "U2") (pin "48") (pinfunction "PIO1_16/~{RI}/CT16B0_CAP0_48") (pintype "bidirectional"))
    )
    (net (code "74") (name "PRESSURE") (class "Default")
      (node (ref "MPX") (pin "P$4") (pinfunction "VOUT_P$4") (pintype "bidirectional"))
      (node (ref "U1") (pin "6") (pinfunction "IO34_6") (pintype "bidirectional"))
    )
    (net (code "75") (name "TSOP") (class "Default")
      (node (ref "U$2") (pin "OUT") (pinfunction "OUT_OUT") (pintype "bidirectional"))
      (node (ref "U1") (pin "31") (pinfunction "IO19_31") (pintype "bidirectional"))
    )
    (net (code "76") (name "USB_DM") (class "Default")
      (node (ref "D7") (pin "3") (pinfunction "C1A2_3") (pintype "passive"))
      (node (ref "R5") (pin "2") (pinfunction "2_2") (pintype "passive"))
      (node (ref "U2") (pin "19") (pinfunction "USB_DM_19") (pintype "bidirectional"))
    )
    (net (code "77") (name "USB_DP") (class "Default")
      (node (ref "D8") (pin "3") (pinfunction "C1A2_3") (pintype "passive"))
      (node (ref "R11") (pin "1") (pinfunction "1_1") (pintype "passive"))
      (node (ref "R6") (pin "2") (pinfunction "2_2") (pintype "passive"))
      (node (ref "U2") (pin "20") (pinfunction "USB_DP_20") (pintype "bidirectional"))
    )
    (net (code "78") (name "unconnected-(IC2B-SYNC-Pad2)") (class "Default")
      (node (ref "IC2") (pin "2") (pinfunction "SYNC_2") (pintype "input"))
    )
    (net (code "79") (name "unconnected-(IC2B-VREF-Pad6)") (class "Default")
      (node (ref "IC2") (pin "6") (pinfunction "VREF_6") (pintype "input"))
    )
    (net (code "80") (name "unconnected-(MPX-1-PadP$1)") (class "Default")
      (node (ref "MPX") (pin "P$1") (pinfunction "1_P$1") (pintype "no_connect"))
    )
    (net (code "81") (name "unconnected-(MPX-5-PadP$5)") (class "Default")
      (node (ref "MPX") (pin "P$5") (pinfunction "5_P$5") (pintype "no_connect"))
    )
    (net (code "82") (name "unconnected-(MPX-6-PadP$6)") (class "Default")
      (node (ref "MPX") (pin "P$6") (pinfunction "6_P$6") (pintype "no_connect"))
    )
    (net (code "83") (name "unconnected-(MPX-7-PadP$7)") (class "Default")
      (node (ref "MPX") (pin "P$7") (pinfunction "7_P$7") (pintype "no_connect"))
    )
    (net (code "84") (name "unconnected-(MPX-8-PadP$8)") (class "Default")
      (node (ref "MPX") (pin "P$8") (pinfunction "8_P$8") (pintype "no_connect"))
    )
    (net (code "85") (name "unconnected-(SV1-Pad12)") (class "Default")
      (node (ref "SV1") (pin "12") (pinfunction "12_12") (pintype "passive"))
    )
    (net (code "86") (name "unconnected-(U1-SCK-Pad20)") (class "Default")
      (node (ref "U1") (pin "20") (pinfunction "SCK_20") (pintype "bidirectional"))
    )
    (net (code "87") (name "unconnected-(U1-SCS-Pad19)") (class "Default")
      (node (ref "U1") (pin "19") (pinfunction "SCS_19") (pintype "bidirectional"))
    )
    (net (code "88") (name "unconnected-(U1-SDI-Pad22)") (class "Default")
      (node (ref "U1") (pin "22") (pinfunction "SDI_22") (pintype "bidirectional"))
    )
    (net (code "89") (name "unconnected-(U1-SDO-Pad21)") (class "Default")
      (node (ref "U1") (pin "21") (pinfunction "SDO_21") (pintype "bidirectional"))
    )
    (net (code "90") (name "unconnected-(U1-SHD-Pad17)") (class "Default")
      (node (ref "U1") (pin "17") (pinfunction "SHD_17") (pintype "bidirectional"))
    )
    (net (code "91") (name "unconnected-(U1-SWP-Pad18)") (class "Default")
      (node (ref "U1") (pin "18") (pinfunction "SWP_18") (pintype "bidirectional"))
    )
    (net (code "92") (name "unconnected-(U2-(PIO1_5{slash}CT32B1_CAP1)PIO1_31-Pad25)") (class "Default")
      (node (ref "U2") (pin "25") (pinfunction "(PIO1_5/CT32B1_CAP1)PIO1_31_25") (pintype "bidirectional"))
    )
    (net (code "93") (name "unconnected-(U2-PIO0_1{slash}CLKOUT{slash}CT32B0_MAT2{slash}USB_FTOGGLE-Pad4)") (class "Default")
      (node (ref "U2") (pin "4") (pinfunction "PIO0_1/CLKOUT/CT32B0_MAT2/USB_FTOGGLE_4") (pintype "bidirectional"))
    )
    (net (code "94") (name "unconnected-(U2-PIO0_2{slash}SSEL0{slash}CT16B0_CAP0-Pad10)") (class "Default")
      (node (ref "U2") (pin "10") (pinfunction "PIO0_2/SSEL0/CT16B0_CAP0_10") (pintype "bidirectional"))
    )
    (net (code "95") (name "unconnected-(U2-PIO0_4{slash}SCL-Pad15)") (class "Default")
      (node (ref "U2") (pin "15") (pinfunction "PIO0_4/SCL_15") (pintype "bidirectional"))
    )
    (net (code "96") (name "unconnected-(U2-PIO0_5{slash}SDA-Pad16)") (class "Default")
      (node (ref "U2") (pin "16") (pinfunction "PIO0_5/SDA_16") (pintype "bidirectional"))
    )
    (net (code "97") (name "unconnected-(U2-PIO0_6{slash}~{USB_CONNECT}{slash}SCK0-Pad22)") (class "Default")
      (node (ref "U2") (pin "22") (pinfunction "PIO0_6/~{USB_CONNECT}/SCK0_22") (pintype "bidirectional"))
    )
    (net (code "98") (name "unconnected-(U2-PIO0_7{slash}~{CTS}-Pad23)") (class "Default")
      (node (ref "U2") (pin "23") (pinfunction "PIO0_7/~{CTS}_23") (pintype "bidirectional"))
    )
    (net (code "99") (name "unconnected-(U2-PIO0_8{slash}MISO0{slash}CT16B0_MAT0-Pad27)") (class "Default")
      (node (ref "U2") (pin "27") (pinfunction "PIO0_8/MISO0/CT16B0_MAT0_27") (pintype "bidirectional"))
    )
    (net (code "100") (name "unconnected-(U2-PIO0_16{slash}AD5{slash}CT32B1_MAT3{slash}WAKEUP-Pad40)") (class "Default")
      (node (ref "U2") (pin "40") (pinfunction "PIO0_16/AD5/CT32B1_MAT3/WAKEUP_40") (pintype "bidirectional"))
    )
    (net (code "101") (name "unconnected-(U2-PIO0_20{slash}CT16B1_CAP0-Pad9)") (class "Default")
      (node (ref "U2") (pin "9") (pinfunction "PIO0_20/CT16B1_CAP0_9") (pintype "bidirectional"))
    )
    (net (code "102") (name "unconnected-(U2-PIO0_21{slash}CT16B1_MAT0{slash}MOSI1-Pad17)") (class "Default")
      (node (ref "U2") (pin "17") (pinfunction "PIO0_21/CT16B1_MAT0/MOSI1_17") (pintype "bidirectional"))
    )
    (net (code "103") (name "unconnected-(U2-PIO0_22{slash}AD6{slash}CT16B1_MAT1{slash}MISO1-Pad30)") (class "Default")
      (node (ref "U2") (pin "30") (pinfunction "PIO0_22/AD6/CT16B1_MAT1/MISO1_30") (pintype "bidirectional"))
    )
    (net (code "104") (name "unconnected-(U2-PIO0_23{slash}AD7-Pad42)") (class "Default")
      (node (ref "U2") (pin "42") (pinfunction "PIO0_23/AD7_42") (pintype "bidirectional"))
    )
    (net (code "105") (name "unconnected-(U2-PIO1_13{slash}~{DTR}{slash}CT16B0_MAT0{slash}TXD-Pad36)") (class "Default")
      (node (ref "U2") (pin "36") (pinfunction "PIO1_13/~{DTR}/CT16B0_MAT0/TXD_36") (pintype "bidirectional"))
    )
    (net (code "106") (name "unconnected-(U2-PIO1_14{slash}~{DSR}{slash}CT16B0_MAT1{slash}RXD-Pad37)") (class "Default")
      (node (ref "U2") (pin "37") (pinfunction "PIO1_14/~{DSR}/CT16B0_MAT1/RXD_37") (pintype "bidirectional"))
    )
    (net (code "107") (name "unconnected-(U2-PIO1_15{slash}~{DCD}{slash}CT16B0_MAT2{slash}SCK1-Pad43)") (class "Default")
      (node (ref "U2") (pin "43") (pinfunction "PIO1_15/~{DCD}/CT16B0_MAT2/SCK1_43") (pintype "bidirectional"))
    )
    (net (code "108") (name "unconnected-(U2-PIO1_19{slash}~{DTR}{slash}SSEL1-Pad2)") (class "Default")
      (node (ref "U2") (pin "2") (pinfunction "PIO1_19/~{DTR}/SSEL1_2") (pintype "bidirectional"))
    )
    (net (code "109") (name "unconnected-(U2-PIO1_20{slash}~{DSR}{slash}SCK1-Pad13)") (class "Default")
      (node (ref "U2") (pin "13") (pinfunction "PIO1_20/~{DSR}/SCK1_13") (pintype "bidirectional"))
    )
    (net (code "110") (name "unconnected-(U2-PIO1_21{slash}~{DCD}{slash}MISO1-Pad26)") (class "Default")
      (node (ref "U2") (pin "26") (pinfunction "PIO1_21/~{DCD}/MISO1_26") (pintype "bidirectional"))
    )
    (net (code "111") (name "unconnected-(U2-PIO1_22{slash}~{RI}{slash}MOSI1-Pad38)") (class "Default")
      (node (ref "U2") (pin "38") (pinfunction "PIO1_22/~{RI}/MOSI1_38") (pintype "bidirectional"))
    )
    (net (code "112") (name "unconnected-(U2-PIO1_23{slash}CT16B1_MAT1{slash}SSEL1-Pad18)") (class "Default")
      (node (ref "U2") (pin "18") (pinfunction "PIO1_23/CT16B1_MAT1/SSEL1_18") (pintype "bidirectional"))
    )
    (net (code "113") (name "unconnected-(U2-PIO1_24{slash}CT32B0_MAT0-Pad21)") (class "Default")
      (node (ref "U2") (pin "21") (pinfunction "PIO1_24/CT32B0_MAT0_21") (pintype "bidirectional"))
    )
    (net (code "114") (name "unconnected-(U2-PIO1_25{slash}CT32B0_MAT1-Pad1)") (class "Default")
      (node (ref "U2") (pin "1") (pinfunction "PIO1_25/CT32B0_MAT1_1") (pintype "bidirectional"))
    )
    (net (code "115") (name "unconnected-(U2-PIO1_26{slash}CT32B0_MAT2{slash}RXD-Pad11)") (class "Default")
      (node (ref "U2") (pin "11") (pinfunction "PIO1_26/CT32B0_MAT2/RXD_11") (pintype "bidirectional"))
    )
    (net (code "116") (name "unconnected-(U2-PIO1_27{slash}CT32B0_MAT3{slash}TXD-Pad12)") (class "Default")
      (node (ref "U2") (pin "12") (pinfunction "PIO1_27/CT32B0_MAT3/TXD_12") (pintype "bidirectional"))
    )
    (net (code "117") (name "unconnected-(U2-PIO1_28{slash}CT32B0_CAP0{slash}SCLK-Pad24)") (class "Default")
      (node (ref "U2") (pin "24") (pinfunction "PIO1_28/CT32B0_CAP0/SCLK_24") (pintype "bidirectional"))
    )
    (net (code "118") (name "unconnected-(U2-PIO1_29{slash}SCK0{slash}CT32B0_CAP1-Pad31)") (class "Default")
      (node (ref "U2") (pin "31") (pinfunction "PIO1_29/SCK0/CT32B0_CAP1_31") (pintype "bidirectional"))
    )
    (net (code "119") (name "unconnected-(U2-TDI{slash}PIO0_11{slash}AD0{slash}CT32B0_MAT3-Pad32)") (class "Default")
      (node (ref "U2") (pin "32") (pinfunction "TDI/PIO0_11/AD0/CT32B0_MAT3_32") (pintype "bidirectional"))
    )
    (net (code "120") (name "unconnected-(U2-TDO{slash}PIO0_13{slash}AD2{slash}CT32B1_MAT0-Pad34)") (class "Default")
      (node (ref "U2") (pin "34") (pinfunction "TDO/PIO0_13/AD2/CT32B1_MAT0_34") (pintype "bidirectional"))
    )
    (net (code "121") (name "unconnected-(U2-TMS{slash}PIO0_12{slash}AD1{slash}CT32B1_CAP0-Pad33)") (class "Default")
      (node (ref "U2") (pin "33") (pinfunction "TMS/PIO0_12/AD1/CT32B1_CAP0_33") (pintype "bidirectional"))
    )
    (net (code "122") (name "unconnected-(U2-~{TRST}{slash}PIO0_14{slash}AD3{slash}CT32B1_MAT1-Pad35)") (class "Default")
      (node (ref "U2") (pin "35") (pinfunction "~{TRST}/PIO0_14/AD3/CT32B1_MAT1_35") (pintype "bidirectional"))
    )
    (net (code "123") (name "unconnected-(U3-USBID-PadID1)") (class "Default")
      (node (ref "U3") (pin "ID1") (pinfunction "USBID_ID1") (pintype "bidirectional"))
    )
    (net (code "124") (name "unconnected-(X2-2-Pad2@2)") (class "Default")
      (node (ref "X2") (pin "2@2") (pinfunction "2_2@2") (pintype "passive"))
    )
    (net (code "125") (name "unconnected-(X3-2-Pad2@2)") (class "Default")
      (node (ref "X3") (pin "2@2") (pinfunction "2_2@2") (pintype "passive"))
    )
  )
)
